# Power02.net
KiCad netlist of a schematic drawn in Altium Designer
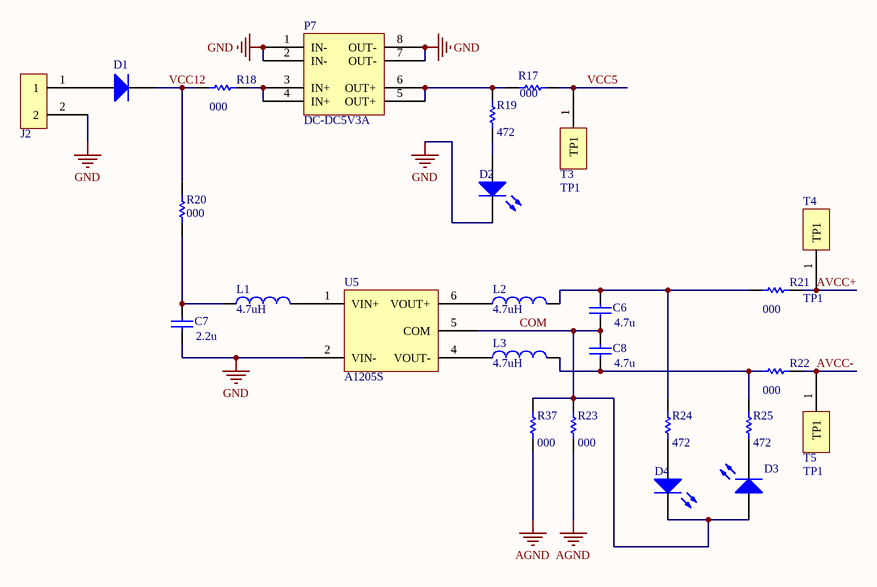
[diagram p0: Power02.SchDoc]

(export (version "E")
  (design (tool "Eeschema 10.0.6"))
  (components
    (comp (ref "C6")
      (value "4.7u")
      (footprint "1206")
      (description "Capacitor (Semiconductor SIM Model)")
      (fields (field (name "Comment") "Cap Semi") (field (name "PUBLISHER") "Altium Limited"))
      (libsource (lib "Miscellaneous Devices") (part "Cap Semi"))
    )
    (comp (ref "C7")
      (value "2.2u")
      (footprint "1206")
      (description "Capacitor (Semiconductor SIM Model)")
      (fields (field (name "Comment") "Cap Semi") (field (name "PUBLISHER") "Altium Limited"))
      (libsource (lib "Miscellaneous Devices") (part "Cap Semi"))
    )
    (comp (ref "C8")
      (value "4.7u")
      (footprint "1206")
      (description "Capacitor (Semiconductor SIM Model)")
      (fields (field (name "Comment") "Cap Semi") (field (name "PUBLISHER") "Altium Limited"))
      (libsource (lib "Miscellaneous Devices") (part "Cap Semi"))
    )
    (comp (ref "D1")
      (value "LED2")
      (footprint "1206")
      (description "1 Amp General Purpose Rectifier")
      (fields (field (name "PUBLISHER") "Altium Limited"))
      (libsource (lib "Miscellaneous Devices") (part "Diode 1N4001"))
    )
    (comp (ref "D2")
      (value "LED2")
      (footprint "0805_LED")
      (description "Typical RED, GREEN, YELLOW, AMBER GaAs LED")
      (fields (field (name "PUBLISHER") "Altium Limited"))
      (libsource (lib "Miscellaneous Devices") (part "LED2"))
    )
    (comp (ref "D3")
      (value "LED2")
      (footprint "0805_LED")
      (description "Typical RED, GREEN, YELLOW, AMBER GaAs LED")
      (fields (field (name "PUBLISHER") "Altium Limited"))
      (libsource (lib "Miscellaneous Devices") (part "LED2"))
    )
    (comp (ref "D4")
      (value "LED2")
      (footprint "0805_LED")
      (description "Typical RED, GREEN, YELLOW, AMBER GaAs LED")
      (fields (field (name "PUBLISHER") "Altium Limited"))
      (libsource (lib "Miscellaneous Devices") (part "LED2"))
    )
    (comp (ref "J2") (value "XK7.62-2P") (footprint "XK7.62-2P") (libsource (lib "CHK-I") (part "XK7.62-2P")))
    (comp (ref "L1")
      (value "4.7uH")
      (footprint "1206")
      (description "Inductor")
      (fields (field (name "PUBLISHER") "Altium Limited"))
      (libsource (lib "Miscellaneous Devices") (part "Inductor"))
    )
    (comp (ref "L2")
      (value "4.7uH")
      (footprint "1206")
      (description "Inductor")
      (fields (field (name "PUBLISHER") "Altium Limited"))
      (libsource (lib "Miscellaneous Devices") (part "Inductor"))
    )
    (comp (ref "L3")
      (value "4.7uH")
      (footprint "1206")
      (description "Inductor")
      (fields (field (name "PUBLISHER") "Altium Limited"))
      (libsource (lib "Miscellaneous Devices") (part "Inductor"))
    )
    (comp (ref "P7") (value "DC-DC5V3A") (footprint "DC-DC3A") (libsource (lib "CHK-I") (part "DC-DC3A")))
    (comp (ref "R17")
      (value "000")
      (footprint "1206")
      (description "Semiconductor Resistor")
      (fields (field (name "Comment") "Res Semi") (field (name "PUBLISHER") "Altium Limited"))
      (libsource (lib "Miscellaneous Devices") (part "Res Semi"))
    )
    (comp (ref "R18")
      (value "000")
      (footprint "1206")
      (description "Semiconductor Resistor")
      (fields (field (name "Comment") "Res Semi") (field (name "PUBLISHER") "Altium Limited"))
      (libsource (lib "Miscellaneous Devices") (part "Res Semi"))
    )
    (comp (ref "R19")
      (value "472")
      (footprint "1206")
      (description "Semiconductor Resistor")
      (fields (field (name "Comment") "Res Semi") (field (name "PUBLISHER") "Altium Limited"))
      (libsource (lib "Miscellaneous Devices") (part "Res Semi"))
    )
    (comp (ref "R20")
      (value "000")
      (footprint "1206")
      (description "Semiconductor Resistor")
      (fields (field (name "Comment") "Res Semi") (field (name "PUBLISHER") "Altium Limited"))
      (libsource (lib "Miscellaneous Devices") (part "Res Semi"))
    )
    (comp (ref "R21")
      (value "000")
      (footprint "1206")
      (description "Semiconductor Resistor")
      (fields (field (name "Comment") "Res Semi") (field (name "PUBLISHER") "Altium Limited"))
      (libsource (lib "Miscellaneous Devices") (part "Res Semi"))
    )
    (comp (ref "R22")
      (value "000")
      (footprint "1206")
      (description "Semiconductor Resistor")
      (fields (field (name "Comment") "Res Semi") (field (name "PUBLISHER") "Altium Limited"))
      (libsource (lib "Miscellaneous Devices") (part "Res Semi"))
    )
    (comp (ref "R23")
      (value "000")
      (footprint "1206")
      (description "Semiconductor Resistor")
      (fields (field (name "Comment") "Res Semi") (field (name "PUBLISHER") "Altium Limited"))
      (libsource (lib "Miscellaneous Devices") (part "Res Semi"))
    )
    (comp (ref "R24")
      (value "472")
      (footprint "1206")
      (description "Semiconductor Resistor")
      (fields (field (name "Comment") "Res Semi") (field (name "PUBLISHER") "Altium Limited"))
      (libsource (lib "Miscellaneous Devices") (part "Res Semi"))
    )
    (comp (ref "R25")
      (value "472")
      (footprint "1206")
      (description "Semiconductor Resistor")
      (fields (field (name "Comment") "Res Semi") (field (name "PUBLISHER") "Altium Limited"))
      (libsource (lib "Miscellaneous Devices") (part "Res Semi"))
    )
    (comp (ref "R37")
      (value "000")
      (footprint "1206")
      (description "Semiconductor Resistor")
      (fields (field (name "Comment") "Res Semi") (field (name "PUBLISHER") "Altium Limited"))
      (libsource (lib "Miscellaneous Devices") (part "Res Semi"))
    )
    (comp (ref "T3") (value "TP1") (footprint "TP1") (libsource (lib "CHK-I") (part "TP1")))
    (comp (ref "T4") (value "TP1") (footprint "TP1") (libsource (lib "") (part "TP1_1")))
    (comp (ref "T5") (value "TP1") (footprint "TP1") (libsource (lib "CHK-I") (part "TP1")))
    (comp (ref "U5") (value "A1205S") (footprint "A1205S") (libsource (lib "CHK-I") (part "A1205S")))
  )
  (nets
    (net (code "1") (name "/AVCC+") (class "Default")
      (node (ref "R21") (pin "2") (pinfunction "2_2") (pintype "passive"))
      (node (ref "T4") (pin "1") (pinfunction "TP1_1") (pintype "passive"))
    )
    (net (code "2") (name "/AVCC-") (class "Default")
      (node (ref "R22") (pin "2") (pinfunction "2_2") (pintype "passive"))
      (node (ref "T5") (pin "1") (pinfunction "TP1_1") (pintype "passive"))
    )
    (net (code "3") (name "/COM") (class "Default")
      (node (ref "C6") (pin "1") (pinfunction "1_1") (pintype "passive"))
      (node (ref "C8") (pin "2") (pinfunction "2_2") (pintype "passive"))
      (node (ref "D3") (pin "1") (pinfunction "A_1") (pintype "passive"))
      (node (ref "D4") (pin "2") (pinfunction "K_2") (pintype "passive"))
      (node (ref "R23") (pin "2") (pinfunction "2_2") (pintype "passive"))
      (node (ref "R37") (pin "2") (pinfunction "2_2") (pintype "passive"))
      (node (ref "U5") (pin "5") (pinfunction "COM_5") (pintype "passive"))
    )
    (net (code "4") (name "/VCC5") (class "Default")
      (node (ref "R17") (pin "2") (pinfunction "2_2") (pintype "passive"))
      (node (ref "T3") (pin "1") (pinfunction "TP1_1") (pintype "passive"))
    )
    (net (code "5") (name "/VCC12") (class "Default")
      (node (ref "D1") (pin "2") (pinfunction "K_2") (pintype "passive"))
      (node (ref "R18") (pin "1") (pinfunction "1_1") (pintype "passive"))
      (node (ref "R20") (pin "2") (pinfunction "2_2") (pintype "passive"))
    )
    (net (code "6") (name "AGND") (class "Default")
      (node (ref "R23") (pin "1") (pinfunction "1_1") (pintype "passive"))
      (node (ref "R37") (pin "1") (pinfunction "1_1") (pintype "passive"))
    )
    (net (code "7") (name "GND") (class "Default")
      (node (ref "C7") (pin "1") (pinfunction "1_1") (pintype "passive"))
      (node (ref "D2") (pin "2") (pinfunction "K_2") (pintype "passive"))
      (node (ref "J2") (pin "2") (pinfunction "2_2") (pintype "passive"))
      (node (ref "P7") (pin "1") (pinfunction "IN-_1") (pintype "passive"))
      (node (ref "P7") (pin "2") (pinfunction "IN-_2") (pintype "passive"))
      (node (ref "P7") (pin "7") (pinfunction "OUT-_7") (pintype "passive"))
      (node (ref "P7") (pin "8") (pinfunction "OUT-_8") (pintype "passive"))
      (node (ref "U5") (pin "2") (pinfunction "VIN-_2") (pintype "passive"))
    )
    (net (code "8") (name "Net-(C6-Pad2)") (class "Default")
      (node (ref "C6") (pin "2") (pinfunction "2_2") (pintype "passive"))
      (node (ref "L2") (pin "2") (pinfunction "2_2") (pintype "passive"))
      (node (ref "R21") (pin "1") (pinfunction "1_1") (pintype "passive"))
      (node (ref "R24") (pin "2") (pinfunction "2_2") (pintype "passive"))
    )
    (net (code "9") (name "Net-(C7-Pad2)") (class "Default")
      (node (ref "C7") (pin "2") (pinfunction "2_2") (pintype "passive"))
      (node (ref "L1") (pin "1") (pinfunction "1_1") (pintype "passive"))
      (node (ref "R20") (pin "1") (pinfunction "1_1") (pintype "passive"))
    )
    (net (code "10") (name "Net-(C8-Pad1)") (class "Default")
      (node (ref "C8") (pin "1") (pinfunction "1_1") (pintype "passive"))
      (node (ref "L3") (pin "2") (pinfunction "2_2") (pintype "passive"))
      (node (ref "R22") (pin "1") (pinfunction "1_1") (pintype "passive"))
      (node (ref "R25") (pin "2") (pinfunction "2_2") (pintype "passive"))
    )
    (net (code "11") (name "Net-(D1-A)") (class "Default")
      (node (ref "D1") (pin "1") (pinfunction "A_1") (pintype "passive"))
      (node (ref "J2") (pin "1") (pinfunction "1_1") (pintype "passive"))
    )
    (net (code "12") (name "Net-(D2-A)") (class "Default")
      (node (ref "D2") (pin "1") (pinfunction "A_1") (pintype "passive"))
      (node (ref "R19") (pin "1") (pinfunction "1_1") (pintype "passive"))
    )
    (net (code "13") (name "Net-(D3-K)") (class "Default")
      (node (ref "D3") (pin "2") (pinfunction "K_2") (pintype "passive"))
      (node (ref "R25") (pin "1") (pinfunction "1_1") (pintype "passive"))
    )
    (net (code "14") (name "Net-(D4-A)") (class "Default")
      (node (ref "D4") (pin "1") (pinfunction "A_1") (pintype "passive"))
      (node (ref "R24") (pin "1") (pinfunction "1_1") (pintype "passive"))
    )
    (net (code "15") (name "Net-(P7-IN+-Pad3)") (class "Default")
      (node (ref "P7") (pin "3") (pinfunction "IN+_3") (pintype "passive"))
      (node (ref "P7") (pin "4") (pinfunction "IN+_4") (pintype "passive"))
      (node (ref "R18") (pin "2") (pinfunction "2_2") (pintype "passive"))
    )
    (net (code "16") (name "Net-(P7-OUT+-Pad5)") (class "Default")
      (node (ref "P7") (pin "5") (pinfunction "OUT+_5") (pintype "passive"))
      (node (ref "P7") (pin "6") (pinfunction "OUT+_6") (pintype "passive"))
      (node (ref "R17") (pin "1") (pinfunction "1_1") (pintype "passive"))
      (node (ref "R19") (pin "2") (pinfunction "2_2") (pintype "passive"))
    )
    (net (code "17") (name "Net-(U5-VIN+)") (class "Default")
      (node (ref "L1") (pin "2") (pinfunction "2_2") (pintype "passive"))
      (node (ref "U5") (pin "1") (pinfunction "VIN+_1") (pintype "passive"))
    )
    (net (code "18") (name "Net-(U5-VOUT+)") (class "Default")
      (node (ref "L2") (pin "1") (pinfunction "1_1") (pintype "passive"))
      (node (ref "U5") (pin "6") (pinfunction "VOUT+_6") (pintype "passive"))
    )
    (net (code "19") (name "Net-(U5-VOUT-)") (class "Default")
      (node (ref "L3") (pin "1") (pinfunction "1_1") (pintype "passive"))
      (node (ref "U5") (pin "4") (pinfunction "VOUT-_4") (pintype "passive"))
    )
  )
)
